# box_NU.net
KiCad netlist of a schematic drawn in Altium Designer
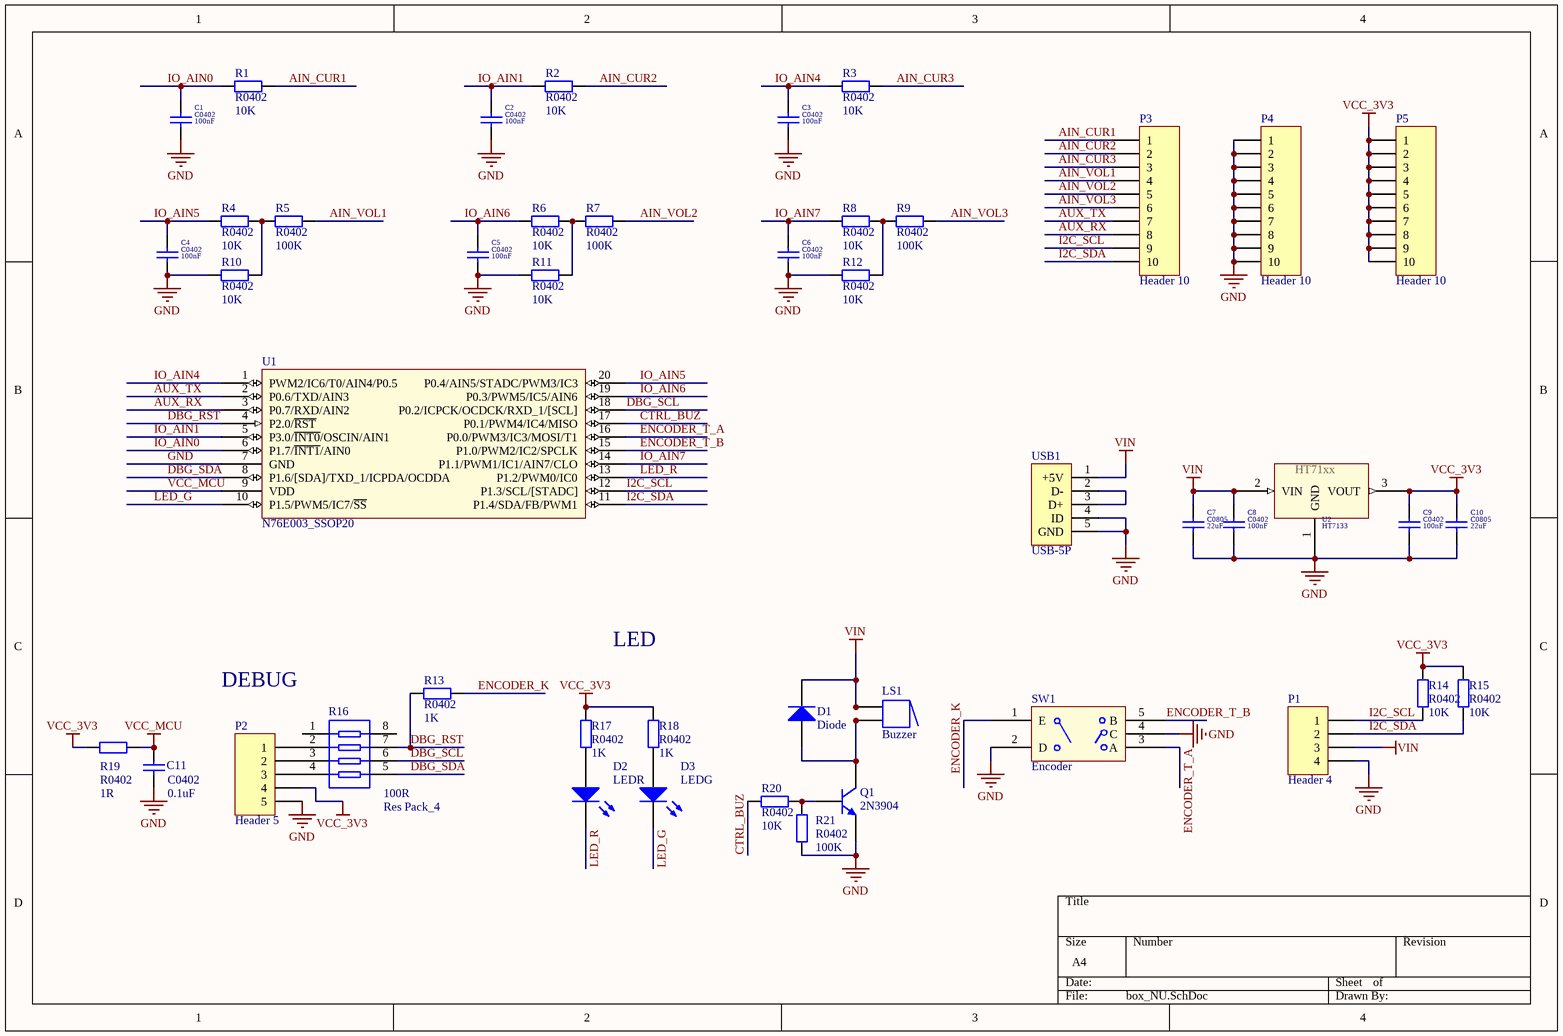
[diagram p0: box_NU.SchDoc]

(export (version "E")
  (design (tool "Eeschema 10.0.6"))
  (components
    (comp (ref "C1")
      (value "C0402")
      (footprint "C 0402")
      (description "Capacitor")
      (fields (field (name "ALTIUM_VALUE") "100nF") (field (name "PUBLISHER") "Altium Limited"))
      (libsource (lib "Miscellaneous Devices") (part "Cap"))
    )
    (comp (ref "C2")
      (value "C0402")
      (footprint "C 0402")
      (description "Capacitor")
      (fields (field (name "ALTIUM_VALUE") "100nF") (field (name "PUBLISHER") "Altium Limited"))
      (libsource (lib "Miscellaneous Devices") (part "Cap"))
    )
    (comp (ref "C3")
      (value "C0402")
      (footprint "C 0402")
      (description "Capacitor")
      (fields (field (name "ALTIUM_VALUE") "100nF") (field (name "PUBLISHER") "Altium Limited"))
      (libsource (lib "Miscellaneous Devices") (part "Cap"))
    )
    (comp (ref "C4")
      (value "C0402")
      (footprint "C 0402")
      (description "Capacitor")
      (fields (field (name "ALTIUM_VALUE") "100nF") (field (name "PUBLISHER") "Altium Limited"))
      (libsource (lib "Miscellaneous Devices") (part "Cap"))
    )
    (comp (ref "C5")
      (value "C0402")
      (footprint "C 0402")
      (description "Capacitor")
      (fields (field (name "ALTIUM_VALUE") "100nF") (field (name "PUBLISHER") "Altium Limited"))
      (libsource (lib "Miscellaneous Devices") (part "Cap"))
    )
    (comp (ref "C6")
      (value "C0402")
      (footprint "C 0402")
      (description "Capacitor")
      (fields (field (name "ALTIUM_VALUE") "100nF") (field (name "PUBLISHER") "Altium Limited"))
      (libsource (lib "Miscellaneous Devices") (part "Cap"))
    )
    (comp (ref "C7")
      (value "C0805")
      (footprint "C 0805")
      (description "Capacitor")
      (fields (field (name "ALTIUM_VALUE") "22uF") (field (name "PUBLISHER") "Altium Limited"))
      (libsource (lib "Miscellaneous Devices") (part "Cap"))
    )
    (comp (ref "C8")
      (value "C0402")
      (footprint "C 0402")
      (description "Capacitor")
      (fields (field (name "ALTIUM_VALUE") "100nF") (field (name "PUBLISHER") "Altium Limited"))
      (libsource (lib "Miscellaneous Devices") (part "Cap"))
    )
    (comp (ref "C9")
      (value "C0402")
      (footprint "C 0402")
      (description "Capacitor")
      (fields (field (name "ALTIUM_VALUE") "100nF") (field (name "PUBLISHER") "Altium Limited"))
      (libsource (lib "Miscellaneous Devices") (part "Cap"))
    )
    (comp (ref "C10")
      (value "C0805")
      (footprint "C 0805")
      (description "Capacitor")
      (fields (field (name "ALTIUM_VALUE") "22uF") (field (name "PUBLISHER") "Altium Limited"))
      (libsource (lib "Miscellaneous Devices") (part "Cap"))
    )
    (comp (ref "C11")
      (value "C0402")
      (footprint "C 0402")
      (description "Capacitor")
      (fields (field (name "ALTIUM_VALUE") "0.1uF") (field (name "PUBLISHER") "Altium Limited"))
      (libsource (lib "Miscellaneous Devices") (part "Cap"))
    )
    (comp (ref "D1")
      (value "Diode")
      (footprint "SMC")
      (description "Default Diode")
      (fields (field (name "PUBLISHER") "Altium Limited"))
      (libsource (lib "Miscellaneous Devices") (part "Diode"))
    )
    (comp (ref "D2")
      (value "LEDR")
      (footprint "LED 0603B")
      (description "Typical INFRARED GaAs LED")
      (fields (field (name "PUBLISHER") "Altium Limited"))
      (libsource (lib "Miscellaneous Devices") (part "LED0"))
    )
    (comp (ref "D3")
      (value "LEDG")
      (footprint "LED 0603B")
      (description "Typical INFRARED GaAs LED")
      (fields (field (name "PUBLISHER") "Altium Limited"))
      (libsource (lib "Miscellaneous Devices") (part "LED0"))
    )
    (comp (ref "LS1")
      (value "Buzzer")
      (footprint "ABSM-1574")
      (description "Magnetic Transducer Buzzer")
      (fields (field (name "PUBLISHER") "Altium Limited"))
      (libsource (lib "Miscellaneous Devices") (part "Buzzer"))
    )
    (comp (ref "P1")
      (value "Header 4")
      (footprint "HDR1X4")
      (description "Header, 4-Pin")
      (fields (field (name "PUBLISHER") "Altium Limited"))
      (libsource (lib "Miscellaneous Connectors") (part "Header 4"))
    )
    (comp (ref "P2")
      (value "Header 5")
      (footprint "HDR1X5")
      (description "Header, 5-Pin")
      (fields (field (name "PUBLISHER") "Altium Limited"))
      (libsource (lib "Connectors") (part "Header 5"))
    )
    (comp (ref "P3")
      (value "Header 10")
      (footprint "HDR1X10")
      (description "Header, 10-Pin")
      (fields (field (name "PUBLISHER") "Altium Limited"))
      (libsource (lib "Miscellaneous Connectors") (part "Header 10"))
    )
    (comp (ref "P4")
      (value "Header 10")
      (footprint "HDR1X10")
      (description "Header, 10-Pin")
      (fields (field (name "PUBLISHER") "Altium Limited"))
      (libsource (lib "Miscellaneous Connectors") (part "Header 10"))
    )
    (comp (ref "P5")
      (value "Header 10")
      (footprint "HDR1X10")
      (description "Header, 10-Pin")
      (fields (field (name "PUBLISHER") "Altium Limited"))
      (libsource (lib "Miscellaneous Connectors") (part "Header 10"))
    )
    (comp (ref "Q1")
      (value "2N3904")
      (footprint "TO-92A")
      (description "NPN General Purpose Amplifier")
      (fields (field (name "PUBLISHER") "Altium Limited"))
      (libsource (lib "Miscellaneous Devices") (part "2N3904"))
    )
    (comp (ref "R1")
      (value "R0402")
      (footprint "R 0402")
      (description "Resistor")
      (fields (field (name "ALTIUM_VALUE") "10K") (field (name "PUBLISHER") "Altium Limited"))
      (libsource (lib "") (part "Res2_1"))
    )
    (comp (ref "R2")
      (value "R0402")
      (footprint "R 0402")
      (description "Resistor")
      (fields (field (name "ALTIUM_VALUE") "10K") (field (name "PUBLISHER") "Altium Limited"))
      (libsource (lib "") (part "Res2_1"))
    )
    (comp (ref "R3")
      (value "R0402")
      (footprint "R 0402")
      (description "Resistor")
      (fields (field (name "ALTIUM_VALUE") "10K") (field (name "PUBLISHER") "Altium Limited"))
      (libsource (lib "") (part "Res2_1"))
    )
    (comp (ref "R4")
      (value "R0402")
      (footprint "R 0402")
      (description "Resistor")
      (fields (field (name "ALTIUM_VALUE") "10K") (field (name "PUBLISHER") "Altium Limited"))
      (libsource (lib "") (part "Res2_1"))
    )
    (comp (ref "R5")
      (value "R0402")
      (footprint "R 0402")
      (description "Resistor")
      (fields (field (name "ALTIUM_VALUE") "100K") (field (name "PUBLISHER") "Altium Limited"))
      (libsource (lib "Miscellaneous Devices") (part "Res2"))
    )
    (comp (ref "R6")
      (value "R0402")
      (footprint "R 0402")
      (description "Resistor")
      (fields (field (name "ALTIUM_VALUE") "10K") (field (name "PUBLISHER") "Altium Limited"))
      (libsource (lib "") (part "Res2_1"))
    )
    (comp (ref "R7")
      (value "R0402")
      (footprint "R 0402")
      (description "Resistor")
      (fields (field (name "ALTIUM_VALUE") "100K") (field (name "PUBLISHER") "Altium Limited"))
      (libsource (lib "Miscellaneous Devices") (part "Res2"))
    )
    (comp (ref "R8")
      (value "R0402")
      (footprint "R 0402")
      (description "Resistor")
      (fields (field (name "ALTIUM_VALUE") "10K") (field (name "PUBLISHER") "Altium Limited"))
      (libsource (lib "") (part "Res2_1"))
    )
    (comp (ref "R9")
      (value "R0402")
      (footprint "R 0402")
      (description "Resistor")
      (fields (field (name "ALTIUM_VALUE") "100K") (field (name "PUBLISHER") "Altium Limited"))
      (libsource (lib "Miscellaneous Devices") (part "Res2"))
    )
    (comp (ref "R10")
      (value "R0402")
      (footprint "R 0402")
      (description "Resistor")
      (fields (field (name "ALTIUM_VALUE") "10K") (field (name "PUBLISHER") "Altium Limited"))
      (libsource (lib "Miscellaneous Devices") (part "Res2"))
    )
    (comp (ref "R11")
      (value "R0402")
      (footprint "R 0402")
      (description "Resistor")
      (fields (field (name "ALTIUM_VALUE") "10K") (field (name "PUBLISHER") "Altium Limited"))
      (libsource (lib "Miscellaneous Devices") (part "Res2"))
    )
    (comp (ref "R12")
      (value "R0402")
      (footprint "R 0402")
      (description "Resistor")
      (fields (field (name "ALTIUM_VALUE") "10K") (field (name "PUBLISHER") "Altium Limited"))
      (libsource (lib "Miscellaneous Devices") (part "Res2"))
    )
    (comp (ref "R13")
      (value "R0402")
      (footprint "R 0402")
      (description "Resistor")
      (fields (field (name "ALTIUM_VALUE") "1K") (field (name "PUBLISHER") "Altium Limited"))
      (libsource (lib "Miscellaneous Devices") (part "Res2"))
    )
    (comp (ref "R14")
      (value "R0402")
      (footprint "R 0402")
      (description "Resistor")
      (fields (field (name "ALTIUM_VALUE") "10K") (field (name "PUBLISHER") "Altium Limited"))
      (libsource (lib "") (part "Res2_2"))
    )
    (comp (ref "R15")
      (value "R0402")
      (footprint "R 0402")
      (description "Resistor")
      (fields (field (name "ALTIUM_VALUE") "10K") (field (name "PUBLISHER") "Altium Limited"))
      (libsource (lib "") (part "Res2_2"))
    )
    (comp (ref "R16")
      (value "Res Pack_4")
      (description "Isolated Resistor Network")
      (fields (field (name "ALTIUM_VALUE") "100R") (field (name "PUBLISHER") "Altium Limited"))
      (libsource (lib "MySchLib") (part "Res Pack_4"))
    )
    (comp (ref "R17")
      (value "R0402")
      (footprint "R 0402")
      (description "Resistor")
      (fields (field (name "ALTIUM_VALUE") "1K") (field (name "PUBLISHER") "Altium Limited"))
      (libsource (lib "") (part "Res2_3"))
    )
    (comp (ref "R18")
      (value "R0402")
      (footprint "R 0402")
      (description "Resistor")
      (fields (field (name "ALTIUM_VALUE") "1K") (field (name "PUBLISHER") "Altium Limited"))
      (libsource (lib "") (part "Res2_3"))
    )
    (comp (ref "R19")
      (value "R0402")
      (footprint "R 0402")
      (description "Resistor")
      (fields (field (name "ALTIUM_VALUE") "1R") (field (name "PUBLISHER") "Altium Limited"))
      (libsource (lib "") (part "Res2_1"))
    )
    (comp (ref "R20")
      (value "R0402")
      (footprint "R 0402")
      (description "Resistor")
      (fields (field (name "ALTIUM_VALUE") "10K") (field (name "PUBLISHER") "Altium Limited"))
      (libsource (lib "Miscellaneous Devices") (part "Res2"))
    )
    (comp (ref "R21")
      (value "R0402")
      (footprint "R 0402")
      (description "Resistor")
      (fields (field (name "ALTIUM_VALUE") "100K") (field (name "PUBLISHER") "Altium Limited"))
      (libsource (lib "") (part "Res2_2"))
    )
    (comp (ref "SW1") (value "Encoder") (description "编码器EC11") (libsource (lib "MySchLib") (part "EC11")))
    (comp (ref "U1")
      (value "N76E003_SSOP20")
      (footprint "SSOP20")
      (description "nuvoton mcu, 20pin")
      (libsource (lib "MySchLib") (part "N76E003_SSOP20"))
    )
    (comp (ref "U2") (value "HT7133") (footprint "SOT89_M") (libsource (lib "MySchLib") (part "HT71xx")))
    (comp (ref "USB1")
      (value "USB-5P")
      (footprint "USB-MICRO_A")
      (description "微型USB母座")
      (fields (field (name "版权归属") "源创客"))
      (libsource (lib "接口类") (part "USB-5P"))
    )
  )
  (nets
    (net (code "1") (name "/AIN_CUR1") (class "Default")
      (node (ref "P3") (pin "1") (pinfunction "1_1") (pintype "passive"))
      (node (ref "R1") (pin "2") (pinfunction "2_2") (pintype "passive"))
    )
    (net (code "2") (name "/AIN_CUR2") (class "Default")
      (node (ref "P3") (pin "2") (pinfunction "2_2") (pintype "passive"))
      (node (ref "R2") (pin "2") (pinfunction "2_2") (pintype "passive"))
    )
    (net (code "3") (name "/AIN_CUR3") (class "Default")
      (node (ref "P3") (pin "3") (pinfunction "3_3") (pintype "passive"))
      (node (ref "R3") (pin "2") (pinfunction "2_2") (pintype "passive"))
    )
    (net (code "4") (name "/AIN_VOL1") (class "Default")
      (node (ref "P3") (pin "4") (pinfunction "4_4") (pintype "passive"))
      (node (ref "R5") (pin "1") (pinfunction "1_1") (pintype "passive"))
    )
    (net (code "5") (name "/AIN_VOL2") (class "Default")
      (node (ref "P3") (pin "5") (pinfunction "5_5") (pintype "passive"))
      (node (ref "R7") (pin "1") (pinfunction "1_1") (pintype "passive"))
    )
    (net (code "6") (name "/AIN_VOL3") (class "Default")
      (node (ref "P3") (pin "6") (pinfunction "6_6") (pintype "passive"))
      (node (ref "R9") (pin "1") (pinfunction "1_1") (pintype "passive"))
    )
    (net (code "7") (name "/AUX_RX") (class "Default")
      (node (ref "P3") (pin "8") (pinfunction "8_8") (pintype "passive"))
      (node (ref "U1") (pin "3") (pinfunction "P0.7/RXD/AIN2_3") (pintype "bidirectional"))
    )
    (net (code "8") (name "/AUX_TX") (class "Default")
      (node (ref "P3") (pin "7") (pinfunction "7_7") (pintype "passive"))
      (node (ref "U1") (pin "2") (pinfunction "P0.6/TXD/AIN3_2") (pintype "bidirectional"))
    )
    (net (code "9") (name "/CTRL_BUZ") (class "Default")
      (node (ref "R20") (pin "2") (pinfunction "2_2") (pintype "passive"))
      (node (ref "U1") (pin "17") (pinfunction "P0.1/PWM4/IC4/MISO_17") (pintype "bidirectional"))
    )
    (net (code "10") (name "/DBG_RST") (class "Default")
      (node (ref "R13") (pin "2") (pinfunction "2_2") (pintype "passive"))
      (node (ref "R16") (pin "7") (pinfunction "7_7") (pintype "passive"))
      (node (ref "U1") (pin "4") (pinfunction "P2.0/~{RST}_4") (pintype "input"))
    )
    (net (code "11") (name "/DBG_SCL") (class "Default")
      (node (ref "R16") (pin "6") (pinfunction "6_6") (pintype "passive"))
      (node (ref "U1") (pin "18") (pinfunction "P0.2/ICPCK/OCDCK/RXD_1/[SCL]_18") (pintype "bidirectional"))
    )
    (net (code "12") (name "/DBG_SDA") (class "Default")
      (node (ref "R16") (pin "5") (pinfunction "5_5") (pintype "passive"))
      (node (ref "U1") (pin "8") (pinfunction "P1.6/[SDA]/TXD_1/ICPDA/OCDDA_8") (pintype "bidirectional"))
    )
    (net (code "13") (name "/ENCODER_K") (class "Default")
      (node (ref "R13") (pin "1") (pinfunction "1_1") (pintype "passive"))
      (node (ref "SW1") (pin "1") (pinfunction "E_1") (pintype "passive"))
    )
    (net (code "14") (name "/ENCODER_T_A") (class "Default")
      (node (ref "SW1") (pin "3") (pinfunction "A_3") (pintype "passive"))
      (node (ref "U1") (pin "16") (pinfunction "P0.0/PWM3/IC3/MOSI/T1_16") (pintype "bidirectional"))
    )
    (net (code "15") (name "/ENCODER_T_B") (class "Default")
      (node (ref "SW1") (pin "5") (pinfunction "B_5") (pintype "passive"))
      (node (ref "U1") (pin "15") (pinfunction "P1.0/PWM2/IC2/SPCLK_15") (pintype "bidirectional"))
    )
    (net (code "16") (name "/I2C_SCL") (class "Default")
      (node (ref "P1") (pin "1") (pinfunction "1_1") (pintype "passive"))
      (node (ref "P3") (pin "9") (pinfunction "9_9") (pintype "passive"))
      (node (ref "R14") (pin "2") (pinfunction "2_2") (pintype "passive"))
      (node (ref "U1") (pin "12") (pinfunction "P1.3/SCL/[STADC]_12") (pintype "bidirectional"))
    )
    (net (code "17") (name "/I2C_SDA") (class "Default")
      (node (ref "P1") (pin "2") (pinfunction "2_2") (pintype "passive"))
      (node (ref "P3") (pin "10") (pinfunction "10_10") (pintype "passive"))
      (node (ref "R15") (pin "2") (pinfunction "2_2") (pintype "passive"))
      (node (ref "U1") (pin "11") (pinfunction "P1.4/SDA/FB/PWM1_11") (pintype "bidirectional"))
    )
    (net (code "18") (name "/IO_AIN0") (class "Default")
      (node (ref "C1") (pin "2") (pinfunction "2_2") (pintype "passive"))
      (node (ref "R1") (pin "1") (pinfunction "1_1") (pintype "passive"))
      (node (ref "U1") (pin "6") (pinfunction "P1.7/~{INT1}/AIN0_6") (pintype "bidirectional"))
    )
    (net (code "19") (name "/IO_AIN1") (class "Default")
      (node (ref "C2") (pin "2") (pinfunction "2_2") (pintype "passive"))
      (node (ref "R2") (pin "1") (pinfunction "1_1") (pintype "passive"))
      (node (ref "U1") (pin "5") (pinfunction "P3.0/~{INT0}/OSCIN/AIN1_5") (pintype "bidirectional"))
    )
    (net (code "20") (name "/IO_AIN4") (class "Default")
      (node (ref "C3") (pin "2") (pinfunction "2_2") (pintype "passive"))
      (node (ref "R3") (pin "1") (pinfunction "1_1") (pintype "passive"))
      (node (ref "U1") (pin "1") (pinfunction "PWM2/IC6/T0/AIN4/P0.5_1") (pintype "bidirectional"))
    )
    (net (code "21") (name "/IO_AIN5") (class "Default")
      (node (ref "C4") (pin "2") (pinfunction "2_2") (pintype "passive"))
      (node (ref "R4") (pin "1") (pinfunction "1_1") (pintype "passive"))
      (node (ref "U1") (pin "20") (pinfunction "P0.4/AIN5/STADC/PWM3/IC3_20") (pintype "bidirectional"))
    )
    (net (code "22") (name "/IO_AIN6") (class "Default")
      (node (ref "C5") (pin "2") (pinfunction "2_2") (pintype "passive"))
      (node (ref "R6") (pin "1") (pinfunction "1_1") (pintype "passive"))
      (node (ref "U1") (pin "19") (pinfunction "P0.3/PWM5/IC5/AIN6_19") (pintype "bidirectional"))
    )
    (net (code "23") (name "/IO_AIN7") (class "Default")
      (node (ref "C6") (pin "2") (pinfunction "2_2") (pintype "passive"))
      (node (ref "R8") (pin "1") (pinfunction "1_1") (pintype "passive"))
      (node (ref "U1") (pin "14") (pinfunction "P1.1/PWM1/IC1/AIN7/CLO_14") (pintype "bidirectional"))
    )
    (net (code "24") (name "/LED_G") (class "Default")
      (node (ref "D3") (pin "2") (pinfunction "K_2") (pintype "passive"))
      (node (ref "U1") (pin "10") (pinfunction "P1.5/PWM5/IC7/~{SS}_10") (pintype "bidirectional"))
    )
    (net (code "25") (name "/LED_R") (class "Default")
      (node (ref "D2") (pin "2") (pinfunction "K_2") (pintype "passive"))
      (node (ref "U1") (pin "13") (pinfunction "P1.2/PWM0/IC0_13") (pintype "bidirectional"))
    )
    (net (code "26") (name "GND") (class "Default")
      (node (ref "C1") (pin "1") (pinfunction "1_1") (pintype "passive"))
      (node (ref "C10") (pin "1") (pinfunction "1_1") (pintype "passive"))
      (node (ref "C11") (pin "1") (pinfunction "1_1") (pintype "passive"))
      (node (ref "C2") (pin "1") (pinfunction "1_1") (pintype "passive"))
      (node (ref "C3") (pin "1") (pinfunction "1_1") (pintype "passive"))
      (node (ref "C4") (pin "1") (pinfunction "1_1") (pintype "passive"))
      (node (ref "C5") (pin "1") (pinfunction "1_1") (pintype "passive"))
      (node (ref "C6") (pin "1") (pinfunction "1_1") (pintype "passive"))
      (node (ref "C7") (pin "1") (pinfunction "1_1") (pintype "passive"))
      (node (ref "C8") (pin "1") (pinfunction "1_1") (pintype "passive"))
      (node (ref "C9") (pin "1") (pinfunction "1_1") (pintype "passive"))
      (node (ref "P1") (pin "4") (pinfunction "4_4") (pintype "passive"))
      (node (ref "P2") (pin "5") (pinfunction "5_5") (pintype "passive"))
      (node (ref "P4") (pin "1") (pinfunction "1_1") (pintype "passive"))
      (node (ref "P4") (pin "10") (pinfunction "10_10") (pintype "passive"))
      (node (ref "P4") (pin "2") (pinfunction "2_2") (pintype "passive"))
      (node (ref "P4") (pin "3") (pinfunction "3_3") (pintype "passive"))
      (node (ref "P4") (pin "4") (pinfunction "4_4") (pintype "passive"))
      (node (ref "P4") (pin "5") (pinfunction "5_5") (pintype "passive"))
      (node (ref "P4") (pin "6") (pinfunction "6_6") (pintype "passive"))
      (node (ref "P4") (pin "7") (pinfunction "7_7") (pintype "passive"))
      (node (ref "P4") (pin "8") (pinfunction "8_8") (pintype "passive"))
      (node (ref "P4") (pin "9") (pinfunction "9_9") (pintype "passive"))
      (node (ref "Q1") (pin "1") (pinfunction "E_1") (pintype "passive"))
      (node (ref "R10") (pin "2") (pinfunction "2_2") (pintype "passive"))
      (node (ref "R11") (pin "2") (pinfunction "2_2") (pintype "passive"))
      (node (ref "R12") (pin "2") (pinfunction "2_2") (pintype "passive"))
      (node (ref "R21") (pin "2") (pinfunction "2_2") (pintype "passive"))
      (node (ref "SW1") (pin "2") (pinfunction "D_2") (pintype "passive"))
      (node (ref "SW1") (pin "4") (pinfunction "C_4") (pintype "passive"))
      (node (ref "U1") (pin "7") (pinfunction "GND_7") (pintype "power_in"))
      (node (ref "U2") (pin "1") (pinfunction "GND_1") (pintype "power_in"))
      (node (ref "USB1") (pin "4") (pinfunction "ID_4") (pintype "passive"))
      (node (ref "USB1") (pin "5") (pinfunction "GND_5") (pintype "passive"))
    )
    (net (code "27") (name "Net-(D1-A)") (class "Default")
      (node (ref "D1") (pin "1") (pinfunction "A_1") (pintype "passive"))
      (node (ref "LS1") (pin "2") (pinfunction "2_2") (pintype "passive"))
      (node (ref "LS1") (pin "2A") (pinfunction "2A_2A") (pintype "passive"))
      (node (ref "Q1") (pin "3") (pinfunction "C_3") (pintype "passive"))
    )
    (net (code "28") (name "Net-(D2-A)") (class "Default")
      (node (ref "D2") (pin "1") (pinfunction "A_1") (pintype "passive"))
      (node (ref "R17") (pin "1") (pinfunction "1_1") (pintype "passive"))
    )
    (net (code "29") (name "Net-(D3-A)") (class "Default")
      (node (ref "D3") (pin "1") (pinfunction "A_1") (pintype "passive"))
      (node (ref "R18") (pin "1") (pinfunction "1_1") (pintype "passive"))
    )
    (net (code "30") (name "Net-(P2-Pad1)") (class "Default")
      (node (ref "P2") (pin "1") (pinfunction "1_1") (pintype "passive"))
      (node (ref "R16") (pin "2") (pinfunction "2_2") (pintype "passive"))
    )
    (net (code "31") (name "Net-(P2-Pad2)") (class "Default")
      (node (ref "P2") (pin "2") (pinfunction "2_2") (pintype "passive"))
      (node (ref "R16") (pin "3") (pinfunction "3_3") (pintype "passive"))
    )
    (net (code "32") (name "Net-(P2-Pad3)") (class "Default")
      (node (ref "P2") (pin "3") (pinfunction "3_3") (pintype "passive"))
      (node (ref "R16") (pin "4") (pinfunction "4_4") (pintype "passive"))
    )
    (net (code "33") (name "Net-(Q1-B)") (class "Default")
      (node (ref "Q1") (pin "2") (pinfunction "B_2") (pintype "passive"))
      (node (ref "R20") (pin "1") (pinfunction "1_1") (pintype "passive"))
      (node (ref "R21") (pin "1") (pinfunction "1_1") (pintype "passive"))
    )
    (net (code "34") (name "Net-(R10-Pad1)") (class "Default")
      (node (ref "R10") (pin "1") (pinfunction "1_1") (pintype "passive"))
      (node (ref "R4") (pin "2") (pinfunction "2_2") (pintype "passive"))
      (node (ref "R5") (pin "2") (pinfunction "2_2") (pintype "passive"))
    )
    (net (code "35") (name "Net-(R11-Pad1)") (class "Default")
      (node (ref "R11") (pin "1") (pinfunction "1_1") (pintype "passive"))
      (node (ref "R6") (pin "2") (pinfunction "2_2") (pintype "passive"))
      (node (ref "R7") (pin "2") (pinfunction "2_2") (pintype "passive"))
    )
    (net (code "36") (name "Net-(R12-Pad1)") (class "Default")
      (node (ref "R12") (pin "1") (pinfunction "1_1") (pintype "passive"))
      (node (ref "R8") (pin "2") (pinfunction "2_2") (pintype "passive"))
      (node (ref "R9") (pin "2") (pinfunction "2_2") (pintype "passive"))
    )
    (net (code "37") (name "Net-(USB1-D+)") (class "Default")
      (node (ref "USB1") (pin "2") (pinfunction "D-_2") (pintype "passive"))
      (node (ref "USB1") (pin "3") (pinfunction "D+_3") (pintype "passive"))
    )
    (net (code "38") (name "VCC_3V3") (class "Default")
      (node (ref "C10") (pin "2") (pinfunction "2_2") (pintype "passive"))
      (node (ref "C9") (pin "2") (pinfunction "2_2") (pintype "passive"))
      (node (ref "P2") (pin "4") (pinfunction "4_4") (pintype "passive"))
      (node (ref "P5") (pin "1") (pinfunction "1_1") (pintype "passive"))
      (node (ref "P5") (pin "10") (pinfunction "10_10") (pintype "passive"))
      (node (ref "P5") (pin "2") (pinfunction "2_2") (pintype "passive"))
      (node (ref "P5") (pin "3") (pinfunction "3_3") (pintype "passive"))
      (node (ref "P5") (pin "4") (pinfunction "4_4") (pintype "passive"))
      (node (ref "P5") (pin "5") (pinfunction "5_5") (pintype "passive"))
      (node (ref "P5") (pin "6") (pinfunction "6_6") (pintype "passive"))
      (node (ref "P5") (pin "7") (pinfunction "7_7") (pintype "passive"))
      (node (ref "P5") (pin "8") (pinfunction "8_8") (pintype "passive"))
      (node (ref "P5") (pin "9") (pinfunction "9_9") (pintype "passive"))
      (node (ref "R14") (pin "1") (pinfunction "1_1") (pintype "passive"))
      (node (ref "R15") (pin "1") (pinfunction "1_1") (pintype "passive"))
      (node (ref "R17") (pin "2") (pinfunction "2_2") (pintype "passive"))
      (node (ref "R18") (pin "2") (pinfunction "2_2") (pintype "passive"))
      (node (ref "R19") (pin "1") (pinfunction "1_1") (pintype "passive"))
      (node (ref "U2") (pin "3") (pinfunction "VOUT_3") (pintype "output"))
    )
    (net (code "39") (name "VCC_MCU") (class "Default")
      (node (ref "C11") (pin "2") (pinfunction "2_2") (pintype "passive"))
      (node (ref "R19") (pin "2") (pinfunction "2_2") (pintype "passive"))
      (node (ref "U1") (pin "9") (pinfunction "VDD_9") (pintype "power_in"))
    )
    (net (code "40") (name "VIN") (class "Default")
      (node (ref "C7") (pin "2") (pinfunction "2_2") (pintype "passive"))
      (node (ref "C8") (pin "2") (pinfunction "2_2") (pintype "passive"))
      (node (ref "D1") (pin "2") (pinfunction "K_2") (pintype "passive"))
      (node (ref "LS1") (pin "1") (pinfunction "1_1") (pintype "passive"))
      (node (ref "LS1") (pin "1A") (pinfunction "1A_1A") (pintype "passive"))
      (node (ref "P1") (pin "3") (pinfunction "3_3") (pintype "passive"))
      (node (ref "U2") (pin "2") (pinfunction "VIN_2") (pintype "input"))
      (node (ref "USB1") (pin "1") (pinfunction "+5V_1") (pintype "passive"))
    )
    (net (code "41") (name "unconnected-(R16-Pad1)") (class "Default")
      (node (ref "R16") (pin "1") (pinfunction "1_1") (pintype "passive"))
    )
    (net (code "42") (name "unconnected-(R16-Pad8)") (class "Default")
      (node (ref "R16") (pin "8") (pinfunction "8_8") (pintype "passive"))
    )
  )
)
